# SPI_HD44780.net
KiCad netlist of a schematic drawn in EAGLE
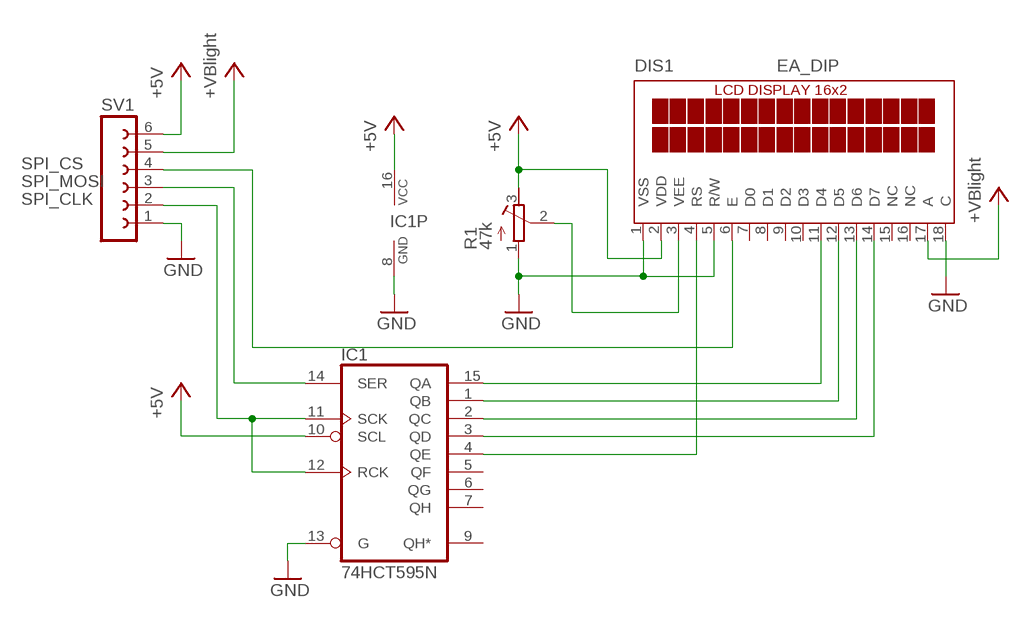
[diagram p0: schematic, sheet 1]

(export (version "E")
  (design (tool "Eeschema 10.0.6"))
  (components
    (comp (ref "DIS1")
      (value "EA_DIP")
      (footprint "eagle-import:EA_DIP")
      (libsource (lib "eagle-import") (part "EA_DIP"))
    )
    (comp (ref "IC1")
      (value "74HCT595N")
      (footprint "eagle-import:DIL16")
      (libsource (lib "eagle-import") (part "74595NHCT"))
    )
    (comp (ref "R1")
      (value "47k")
      (footprint "eagle-import:RTRIM3339P")
      (libsource (lib "eagle-import") (part "R-TRIMM3339P"))
    )
    (comp (ref "SV1")
      (value "FE06-1")
      (footprint "eagle-import:FE06")
      (libsource (lib "eagle-import") (part "FE06-1"))
    )
  )
  (nets
    (net (code "1") (name "+5V") (class "Default")
      (node (ref "DIS1") (pin "2") (pinfunction "VDD_2") (pintype "power_in"))
      (node (ref "IC1") (pin "10") (pinfunction "SCL_10") (pintype "input"))
      (node (ref "IC1") (pin "16") (pinfunction "VCC_16") (pintype "power_in"))
      (node (ref "R1") (pin "3") (pinfunction "E_3") (pintype "passive"))
      (node (ref "SV1") (pin "6") (pinfunction "6_6") (pintype "passive"))
    )
    (net (code "2") (name "+VBlight") (class "Default")
      (node (ref "DIS1") (pin "17") (pinfunction "A_17") (pintype "passive"))
      (node (ref "SV1") (pin "5") (pinfunction "5_5") (pintype "passive"))
    )
    (net (code "3") (name "/SPI_CLK") (class "Default")
      (node (ref "IC1") (pin "11") (pinfunction "SCK_11") (pintype "input"))
      (node (ref "IC1") (pin "12") (pinfunction "RCK_12") (pintype "input"))
      (node (ref "SV1") (pin "2") (pinfunction "2_2") (pintype "passive"))
    )
    (net (code "4") (name "/SPI_CS") (class "Default")
      (node (ref "DIS1") (pin "6") (pinfunction "E_6") (pintype "input"))
      (node (ref "SV1") (pin "4") (pinfunction "4_4") (pintype "passive"))
    )
    (net (code "5") (name "/SPI_MOSI") (class "Default")
      (node (ref "IC1") (pin "14") (pinfunction "SER_14") (pintype "input"))
      (node (ref "SV1") (pin "3") (pinfunction "3_3") (pintype "passive"))
    )
    (net (code "6") (name "GND") (class "Default")
      (node (ref "DIS1") (pin "1") (pinfunction "VSS_1") (pintype "power_in"))
      (node (ref "DIS1") (pin "18") (pinfunction "C_18") (pintype "passive"))
      (node (ref "DIS1") (pin "5") (pinfunction "R/W_5") (pintype "input"))
      (node (ref "IC1") (pin "13") (pinfunction "G_13") (pintype "input"))
      (node (ref "IC1") (pin "8") (pinfunction "GND_8") (pintype "power_in"))
      (node (ref "R1") (pin "1") (pinfunction "A_1") (pintype "passive"))
      (node (ref "SV1") (pin "1") (pinfunction "1_1") (pintype "passive"))
    )
    (net (code "7") (name "Net-(DIS1-D4)") (class "Default")
      (node (ref "DIS1") (pin "11") (pinfunction "D4_11") (pintype "input"))
      (node (ref "IC1") (pin "15") (pinfunction "QA_15") (pintype "tri_state"))
    )
    (net (code "8") (name "Net-(DIS1-D5)") (class "Default")
      (node (ref "DIS1") (pin "12") (pinfunction "D5_12") (pintype "input"))
      (node (ref "IC1") (pin "1") (pinfunction "QB_1") (pintype "tri_state"))
    )
    (net (code "9") (name "Net-(DIS1-D6)") (class "Default")
      (node (ref "DIS1") (pin "13") (pinfunction "D6_13") (pintype "input"))
      (node (ref "IC1") (pin "2") (pinfunction "QC_2") (pintype "tri_state"))
    )
    (net (code "10") (name "Net-(DIS1-D7)") (class "Default")
      (node (ref "DIS1") (pin "14") (pinfunction "D7_14") (pintype "input"))
      (node (ref "IC1") (pin "3") (pinfunction "QD_3") (pintype "tri_state"))
    )
    (net (code "11") (name "Net-(DIS1-RS)") (class "Default")
      (node (ref "DIS1") (pin "4") (pinfunction "RS_4") (pintype "input"))
      (node (ref "IC1") (pin "4") (pinfunction "QE_4") (pintype "tri_state"))
    )
    (net (code "12") (name "Net-(DIS1-VEE)") (class "Default")
      (node (ref "DIS1") (pin "3") (pinfunction "VEE_3") (pintype "power_in"))
      (node (ref "R1") (pin "2") (pinfunction "S_2") (pintype "passive"))
    )
    (net (code "13") (name "unconnected-(DIS1-D0-Pad7)") (class "Default")
      (node (ref "DIS1") (pin "7") (pinfunction "D0_7") (pintype "input"))
    )
    (net (code "14") (name "unconnected-(DIS1-D1-Pad8)") (class "Default")
      (node (ref "DIS1") (pin "8") (pinfunction "D1_8") (pintype "input"))
    )
    (net (code "15") (name "unconnected-(DIS1-D2-Pad9)") (class "Default")
      (node (ref "DIS1") (pin "9") (pinfunction "D2_9") (pintype "input"))
    )
    (net (code "16") (name "unconnected-(DIS1-D3-Pad10)") (class "Default")
      (node (ref "DIS1") (pin "10") (pinfunction "D3_10") (pintype "input"))
    )
    (net (code "17") (name "unconnected-(DIS1-NC-Pad15)") (class "Default")
      (node (ref "DIS1") (pin "15") (pinfunction "NC_15") (pintype "no_connect"))
    )
    (net (code "18") (name "unconnected-(DIS1-NC-Pad16)") (class "Default")
      (node (ref "DIS1") (pin "16") (pinfunction "NC_16") (pintype "no_connect"))
    )
    (net (code "19") (name "unconnected-(IC1A-QF-Pad5)") (class "Default")
      (node (ref "IC1") (pin "5") (pinfunction "QF_5") (pintype "tri_state"))
    )
    (net (code "20") (name "unconnected-(IC1A-QG-Pad6)") (class "Default")
      (node (ref "IC1") (pin "6") (pinfunction "QG_6") (pintype "tri_state"))
    )
    (net (code "21") (name "unconnected-(IC1A-QH*-Pad9)") (class "Default")
      (node (ref "IC1") (pin "9") (pinfunction "QH*_9") (pintype "tri_state"))
    )
    (net (code "22") (name "unconnected-(IC1A-QH-Pad7)") (class "Default")
      (node (ref "IC1") (pin "7") (pinfunction "QH_7") (pintype "tri_state"))
    )
  )
)
